# TDRPulseGen_RevC.net
KiCad netlist of a schematic drawn in EAGLE
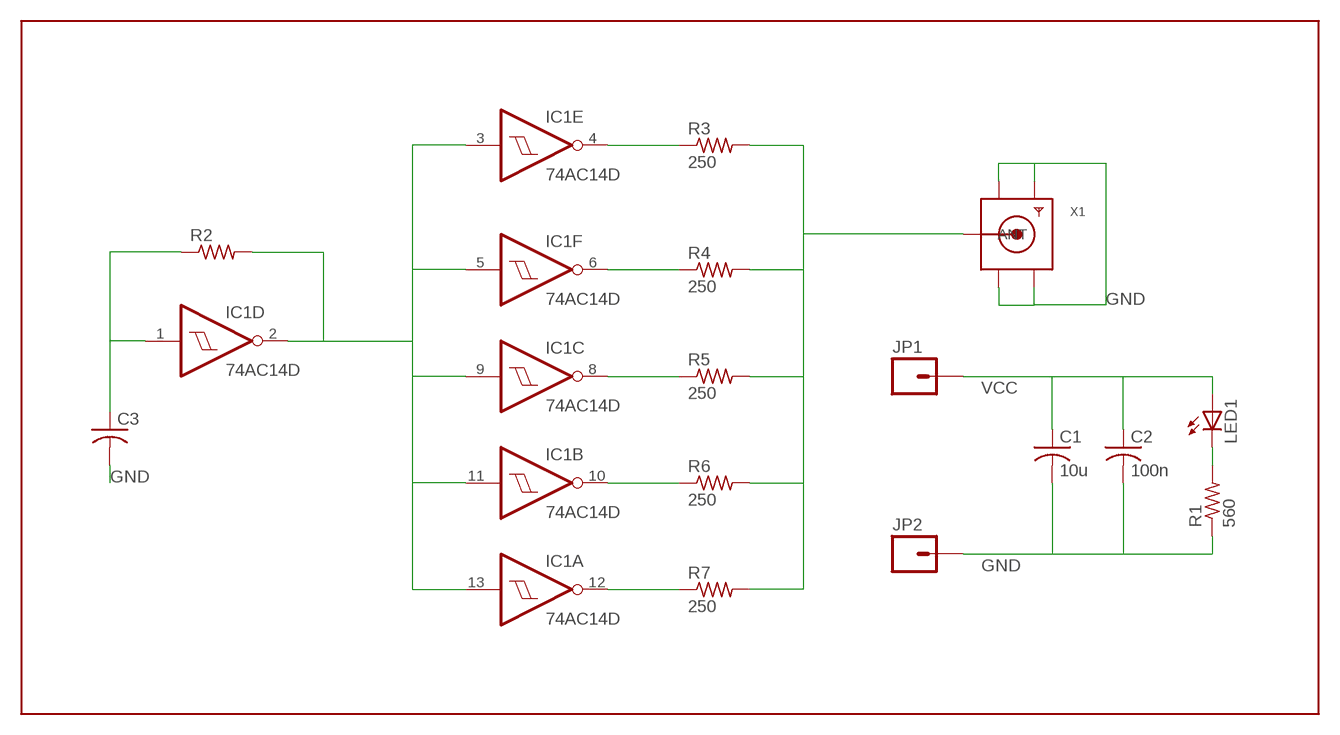
[diagram p0: schematic, sheet 1]

(export (version "E")
  (design (tool "Eeschema 10.0.6"))
  (components
    (comp (ref "C1")
      (value "10u")
      (footprint "eagle-import:C0805")
      (libsource (lib "eagle-import") (part "C-USC0805"))
    )
    (comp (ref "C2")
      (value "100n")
      (footprint "eagle-import:C0805")
      (libsource (lib "eagle-import") (part "C-USC0805"))
    )
    (comp (ref "C3")
      (value "C-USC0805")
      (footprint "eagle-import:C0805")
      (libsource (lib "eagle-import") (part "C-USC0805"))
    )
    (comp (ref "IC1")
      (value "74AC14D")
      (footprint "eagle-import:SO14")
      (libsource (lib "eagle-import") (part "7414DAC"))
    )
    (comp (ref "JP1")
      (value "M01PTH")
      (footprint "eagle-import:1X01")
      (libsource (lib "eagle-import") (part "M01PTH"))
    )
    (comp (ref "JP2")
      (value "M01PTH")
      (footprint "eagle-import:1X01")
      (libsource (lib "eagle-import") (part "M01PTH"))
    )
    (comp (ref "LED1")
      (value "LEDCHIPLED_0805")
      (footprint "eagle-import:CHIPLED_0805")
      (libsource (lib "eagle-import") (part "LEDCHIPLED_0805"))
    )
    (comp (ref "R1")
      (value "560")
      (footprint "eagle-import:R0805")
      (libsource (lib "eagle-import") (part "R-US_R0805"))
    )
    (comp (ref "R2")
      (value "R-US_R0805")
      (footprint "eagle-import:R0805")
      (libsource (lib "eagle-import") (part "R-US_R0805"))
    )
    (comp (ref "R3")
      (value "250")
      (footprint "eagle-import:R0805")
      (libsource (lib "eagle-import") (part "R-US_R0805"))
    )
    (comp (ref "R4")
      (value "250")
      (footprint "eagle-import:R0805")
      (libsource (lib "eagle-import") (part "R-US_R0805"))
    )
    (comp (ref "R5")
      (value "250")
      (footprint "eagle-import:R0805")
      (libsource (lib "eagle-import") (part "R-US_R0805"))
    )
    (comp (ref "R6")
      (value "250")
      (footprint "eagle-import:R0805")
      (libsource (lib "eagle-import") (part "R-US_R0805"))
    )
    (comp (ref "R7")
      (value "250")
      (footprint "eagle-import:R0805")
      (libsource (lib "eagle-import") (part "R-US_R0805"))
    )
    (comp (ref "X1")
      (value "SMACONNECTOR")
      (footprint "eagle-import:SMA90_DIP")
      (libsource (lib "eagle-import") (part "SMACONNECTOR"))
    )
  )
  (nets
    (net (code "1") (name "/GND") (class "Default")
      (node (ref "C1") (pin "2") (pinfunction "2_2") (pintype "passive"))
      (node (ref "C2") (pin "2") (pinfunction "2_2") (pintype "passive"))
      (node (ref "C3") (pin "2") (pinfunction "2_2") (pintype "passive"))
      (node (ref "JP2") (pin "1") (pinfunction "1_1") (pintype "passive"))
      (node (ref "R1") (pin "1") (pinfunction "1_1") (pintype "passive"))
      (node (ref "X1") (pin "GND1") (pinfunction "GND1_GND1") (pintype "power_in"))
      (node (ref "X1") (pin "GND2") (pinfunction "GND2_GND2") (pintype "power_in"))
      (node (ref "X1") (pin "GND3") (pinfunction "GND3_GND3") (pintype "power_in"))
      (node (ref "X1") (pin "GND4") (pinfunction "GND4_GND4") (pintype "power_in"))
    )
    (net (code "2") (name "/VCC") (class "Default")
      (node (ref "C1") (pin "1") (pinfunction "1_1") (pintype "passive"))
      (node (ref "C2") (pin "1") (pinfunction "1_1") (pintype "passive"))
      (node (ref "JP1") (pin "1") (pinfunction "1_1") (pintype "passive"))
      (node (ref "LED1") (pin "A") (pinfunction "A_A") (pintype "passive"))
    )
    (net (code "3") (name "Net-(IC1A-I)") (class "Default")
      (node (ref "IC1") (pin "11") (pinfunction "I_11") (pintype "input"))
      (node (ref "IC1") (pin "13") (pinfunction "I_13") (pintype "input"))
      (node (ref "IC1") (pin "2") (pinfunction "O_2") (pintype "output"))
      (node (ref "IC1") (pin "3") (pinfunction "I_3") (pintype "input"))
      (node (ref "IC1") (pin "5") (pinfunction "I_5") (pintype "input"))
      (node (ref "IC1") (pin "9") (pinfunction "I_9") (pintype "input"))
      (node (ref "R2") (pin "2") (pinfunction "2_2") (pintype "passive"))
    )
    (net (code "4") (name "Net-(IC1A-O)") (class "Default")
      (node (ref "IC1") (pin "12") (pinfunction "O_12") (pintype "output"))
      (node (ref "R7") (pin "1") (pinfunction "1_1") (pintype "passive"))
    )
    (net (code "5") (name "Net-(IC1B-O)") (class "Default")
      (node (ref "IC1") (pin "10") (pinfunction "O_10") (pintype "output"))
      (node (ref "R6") (pin "1") (pinfunction "1_1") (pintype "passive"))
    )
    (net (code "6") (name "Net-(IC1C-O)") (class "Default")
      (node (ref "IC1") (pin "8") (pinfunction "O_8") (pintype "output"))
      (node (ref "R5") (pin "1") (pinfunction "1_1") (pintype "passive"))
    )
    (net (code "7") (name "Net-(IC1D-I)") (class "Default")
      (node (ref "C3") (pin "1") (pinfunction "1_1") (pintype "passive"))
      (node (ref "IC1") (pin "1") (pinfunction "I_1") (pintype "input"))
      (node (ref "R2") (pin "1") (pinfunction "1_1") (pintype "passive"))
    )
    (net (code "8") (name "Net-(IC1E-O)") (class "Default")
      (node (ref "IC1") (pin "4") (pinfunction "O_4") (pintype "output"))
      (node (ref "R3") (pin "1") (pinfunction "1_1") (pintype "passive"))
    )
    (net (code "9") (name "Net-(IC1F-O)") (class "Default")
      (node (ref "IC1") (pin "6") (pinfunction "O_6") (pintype "output"))
      (node (ref "R4") (pin "1") (pinfunction "1_1") (pintype "passive"))
    )
    (net (code "10") (name "Net-(LED1-PadC)") (class "Default")
      (node (ref "LED1") (pin "C") (pinfunction "C_C") (pintype "passive"))
      (node (ref "R1") (pin "2") (pinfunction "2_2") (pintype "passive"))
    )
    (net (code "11") (name "Net-(X1-ANT)") (class "Default")
      (node (ref "R3") (pin "2") (pinfunction "2_2") (pintype "passive"))
      (node (ref "R4") (pin "2") (pinfunction "2_2") (pintype "passive"))
      (node (ref "R5") (pin "2") (pinfunction "2_2") (pintype "passive"))
      (node (ref "R6") (pin "2") (pinfunction "2_2") (pintype "passive"))
      (node (ref "R7") (pin "2") (pinfunction "2_2") (pintype "passive"))
      (node (ref "X1") (pin "ANTENNA") (pinfunction "ANT_ANTENNA") (pintype "bidirectional"))
    )
  )
)
